# D_Output.net
KiCad netlist of a schematic drawn in Altium Designer
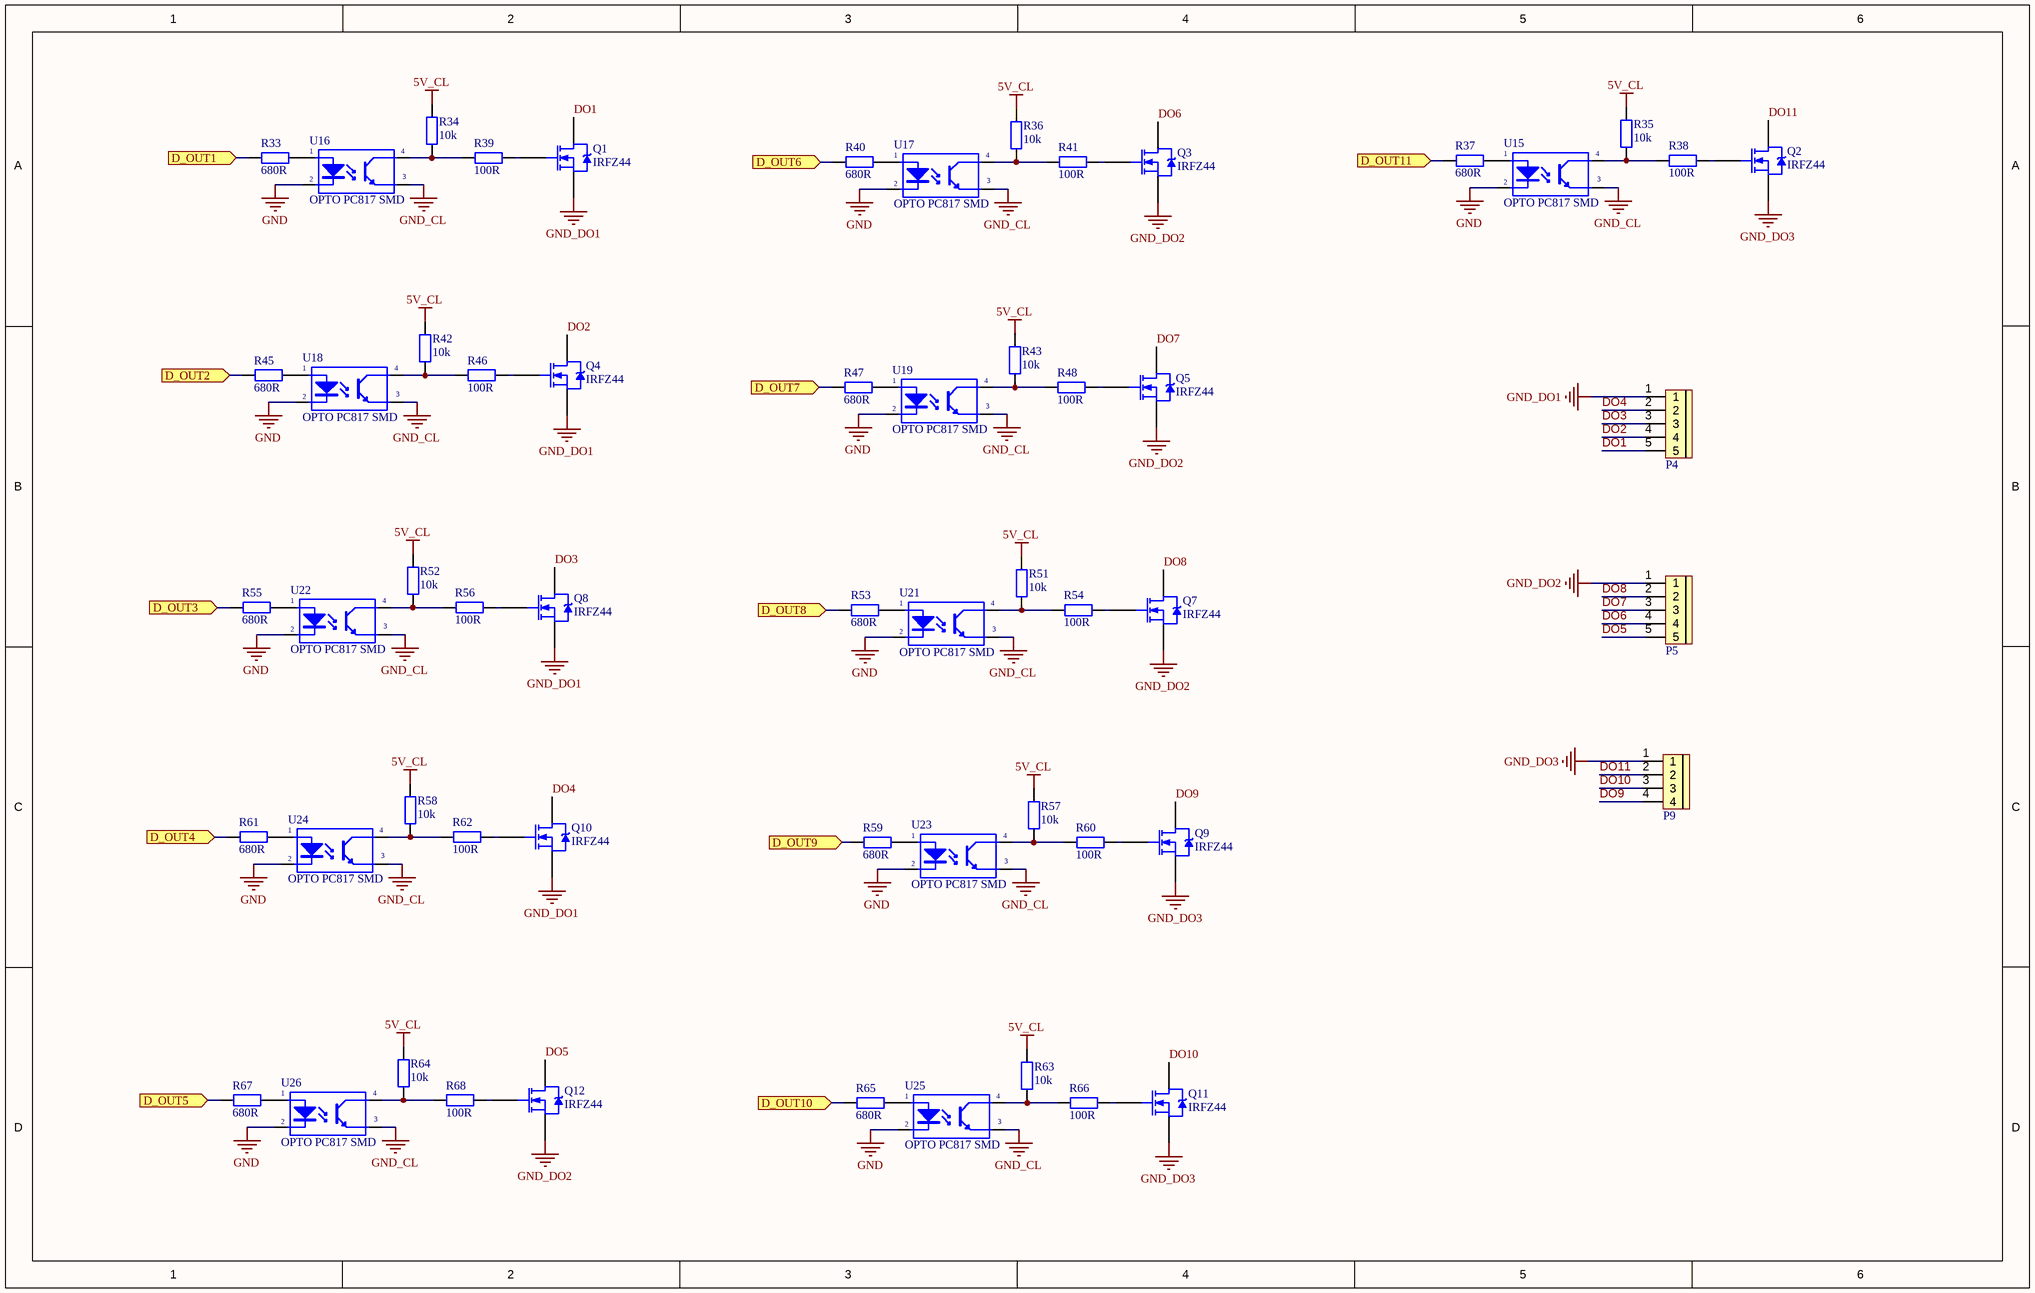
[diagram p0: D_Output.SchDoc]

(export (version "E")
  (design (tool "Eeschema 10.0.6"))
  (components
    (comp (ref "P4")
      (value "CON 5 EDG5.08")
      (footprint "CON 5 5EDG5.08")
      (description "Cắm")
      (libsource (lib "Altium_Lib_by_KhueNguyenCreator") (part "CON 5 EDG5.08"))
    )
    (comp (ref "P5")
      (value "CON 5 EDG5.08")
      (footprint "CON 5 5EDG5.08")
      (description "Cắm")
      (libsource (lib "Altium_Lib_by_KhueNguyenCreator") (part "CON 5 EDG5.08"))
    )
    (comp (ref "P9")
      (value "CON 4 EDG5.08")
      (footprint "CON 4 4EDG5.08")
      (description "Cắm")
      (libsource (lib "Altium_Lib_by_KhueNguyenCreator") (part "CON 4 EDG5.08"))
    )
    (comp (ref "Q1")
      (value "IRFZ44")
      (footprint "TO220")
      (description "N-Channel Power MOSFET")
      (libsource (lib "Altium_Lib_by_KhueNguyenCreator") (part "IRFZ44 DIP"))
    )
    (comp (ref "Q2")
      (value "IRFZ44")
      (footprint "TO220")
      (description "N-Channel Power MOSFET")
      (libsource (lib "Altium_Lib_by_KhueNguyenCreator") (part "IRFZ44 DIP"))
    )
    (comp (ref "Q3")
      (value "IRFZ44")
      (footprint "TO220")
      (description "N-Channel Power MOSFET")
      (libsource (lib "Altium_Lib_by_KhueNguyenCreator") (part "IRFZ44 DIP"))
    )
    (comp (ref "Q4")
      (value "IRFZ44")
      (footprint "TO220")
      (description "N-Channel Power MOSFET")
      (libsource (lib "Altium_Lib_by_KhueNguyenCreator") (part "IRFZ44 DIP"))
    )
    (comp (ref "Q5")
      (value "IRFZ44")
      (footprint "TO220")
      (description "N-Channel Power MOSFET")
      (libsource (lib "Altium_Lib_by_KhueNguyenCreator") (part "IRFZ44 DIP"))
    )
    (comp (ref "Q7")
      (value "IRFZ44")
      (footprint "TO220")
      (description "N-Channel Power MOSFET")
      (libsource (lib "Altium_Lib_by_KhueNguyenCreator") (part "IRFZ44 DIP"))
    )
    (comp (ref "Q8")
      (value "IRFZ44")
      (footprint "TO220")
      (description "N-Channel Power MOSFET")
      (libsource (lib "Altium_Lib_by_KhueNguyenCreator") (part "IRFZ44 DIP"))
    )
    (comp (ref "Q9")
      (value "IRFZ44")
      (footprint "TO220")
      (description "N-Channel Power MOSFET")
      (libsource (lib "Altium_Lib_by_KhueNguyenCreator") (part "IRFZ44 DIP"))
    )
    (comp (ref "Q10")
      (value "IRFZ44")
      (footprint "TO220")
      (description "N-Channel Power MOSFET")
      (libsource (lib "Altium_Lib_by_KhueNguyenCreator") (part "IRFZ44 DIP"))
    )
    (comp (ref "Q11")
      (value "IRFZ44")
      (footprint "TO220")
      (description "N-Channel Power MOSFET")
      (libsource (lib "Altium_Lib_by_KhueNguyenCreator") (part "IRFZ44 DIP"))
    )
    (comp (ref "Q12")
      (value "IRFZ44")
      (footprint "TO220")
      (description "N-Channel Power MOSFET")
      (libsource (lib "Altium_Lib_by_KhueNguyenCreator") (part "IRFZ44 DIP"))
    )
    (comp (ref "R33")
      (value "680R")
      (footprint "tro smd 0805")
      (description "Dán")
      (libsource (lib "Altium_Lib_by_KhueNguyenCreator") (part "Tro 0805 1% 680R"))
    )
    (comp (ref "R34")
      (value "10k")
      (footprint "tro smd 0805")
      (description "Dán")
      (libsource (lib "Altium_Lib_by_KhueNguyenCreator") (part "Tro 0805 1% 10k"))
    )
    (comp (ref "R35")
      (value "10k")
      (footprint "tro smd 0805")
      (description "Dán")
      (libsource (lib "Altium_Lib_by_KhueNguyenCreator") (part "Tro 0805 1% 10k"))
    )
    (comp (ref "R36")
      (value "10k")
      (footprint "tro smd 0805")
      (description "Dán")
      (libsource (lib "Altium_Lib_by_KhueNguyenCreator") (part "Tro 0805 1% 10k"))
    )
    (comp (ref "R37")
      (value "680R")
      (footprint "tro smd 0805")
      (description "Dán")
      (libsource (lib "Altium_Lib_by_KhueNguyenCreator") (part "Tro 0805 1% 680R"))
    )
    (comp (ref "R38")
      (value "100R")
      (footprint "tro smd 0805")
      (description "Dán")
      (libsource (lib "Altium_Lib_by_KhueNguyenCreator") (part "Tro 0805 5% 100R"))
    )
    (comp (ref "R39")
      (value "100R")
      (footprint "tro smd 0805")
      (description "Dán")
      (libsource (lib "Altium_Lib_by_KhueNguyenCreator") (part "Tro 0805 5% 100R"))
    )
    (comp (ref "R40")
      (value "680R")
      (footprint "tro smd 0805")
      (description "Dán")
      (libsource (lib "Altium_Lib_by_KhueNguyenCreator") (part "Tro 0805 1% 680R"))
    )
    (comp (ref "R41")
      (value "100R")
      (footprint "tro smd 0805")
      (description "Dán")
      (libsource (lib "Altium_Lib_by_KhueNguyenCreator") (part "Tro 0805 5% 100R"))
    )
    (comp (ref "R42")
      (value "10k")
      (footprint "tro smd 0805")
      (description "Dán")
      (libsource (lib "Altium_Lib_by_KhueNguyenCreator") (part "Tro 0805 1% 10k"))
    )
    (comp (ref "R43")
      (value "10k")
      (footprint "tro smd 0805")
      (description "Dán")
      (libsource (lib "Altium_Lib_by_KhueNguyenCreator") (part "Tro 0805 1% 10k"))
    )
    (comp (ref "R45")
      (value "680R")
      (footprint "tro smd 0805")
      (description "Dán")
      (libsource (lib "Altium_Lib_by_KhueNguyenCreator") (part "Tro 0805 1% 680R"))
    )
    (comp (ref "R46")
      (value "100R")
      (footprint "tro smd 0805")
      (description "Dán")
      (libsource (lib "Altium_Lib_by_KhueNguyenCreator") (part "Tro 0805 5% 100R"))
    )
    (comp (ref "R47")
      (value "680R")
      (footprint "tro smd 0805")
      (description "Dán")
      (libsource (lib "Altium_Lib_by_KhueNguyenCreator") (part "Tro 0805 1% 680R"))
    )
    (comp (ref "R48")
      (value "100R")
      (footprint "tro smd 0805")
      (description "Dán")
      (libsource (lib "Altium_Lib_by_KhueNguyenCreator") (part "Tro 0805 5% 100R"))
    )
    (comp (ref "R51")
      (value "10k")
      (footprint "tro smd 0805")
      (description "Dán")
      (libsource (lib "Altium_Lib_by_KhueNguyenCreator") (part "Tro 0805 1% 10k"))
    )
    (comp (ref "R52")
      (value "10k")
      (footprint "tro smd 0805")
      (description "Dán")
      (libsource (lib "Altium_Lib_by_KhueNguyenCreator") (part "Tro 0805 1% 10k"))
    )
    (comp (ref "R53")
      (value "680R")
      (footprint "tro smd 0805")
      (description "Dán")
      (libsource (lib "Altium_Lib_by_KhueNguyenCreator") (part "Tro 0805 1% 680R"))
    )
    (comp (ref "R54")
      (value "100R")
      (footprint "tro smd 0805")
      (description "Dán")
      (libsource (lib "Altium_Lib_by_KhueNguyenCreator") (part "Tro 0805 5% 100R"))
    )
    (comp (ref "R55")
      (value "680R")
      (footprint "tro smd 0805")
      (description "Dán")
      (libsource (lib "Altium_Lib_by_KhueNguyenCreator") (part "Tro 0805 1% 680R"))
    )
    (comp (ref "R56")
      (value "100R")
      (footprint "tro smd 0805")
      (description "Dán")
      (libsource (lib "Altium_Lib_by_KhueNguyenCreator") (part "Tro 0805 5% 100R"))
    )
    (comp (ref "R57")
      (value "10k")
      (footprint "tro smd 0805")
      (description "Dán")
      (libsource (lib "Altium_Lib_by_KhueNguyenCreator") (part "Tro 0805 1% 10k"))
    )
    (comp (ref "R58")
      (value "10k")
      (footprint "tro smd 0805")
      (description "Dán")
      (libsource (lib "Altium_Lib_by_KhueNguyenCreator") (part "Tro 0805 1% 10k"))
    )
    (comp (ref "R59")
      (value "680R")
      (footprint "tro smd 0805")
      (description "Dán")
      (libsource (lib "Altium_Lib_by_KhueNguyenCreator") (part "Tro 0805 1% 680R"))
    )
    (comp (ref "R60")
      (value "100R")
      (footprint "tro smd 0805")
      (description "Dán")
      (libsource (lib "Altium_Lib_by_KhueNguyenCreator") (part "Tro 0805 5% 100R"))
    )
    (comp (ref "R61")
      (value "680R")
      (footprint "tro smd 0805")
      (description "Dán")
      (libsource (lib "Altium_Lib_by_KhueNguyenCreator") (part "Tro 0805 1% 680R"))
    )
    (comp (ref "R62")
      (value "100R")
      (footprint "tro smd 0805")
      (description "Dán")
      (libsource (lib "Altium_Lib_by_KhueNguyenCreator") (part "Tro 0805 5% 100R"))
    )
    (comp (ref "R63")
      (value "10k")
      (footprint "tro smd 0805")
      (description "Dán")
      (libsource (lib "Altium_Lib_by_KhueNguyenCreator") (part "Tro 0805 1% 10k"))
    )
    (comp (ref "R64")
      (value "10k")
      (footprint "tro smd 0805")
      (description "Dán")
      (libsource (lib "Altium_Lib_by_KhueNguyenCreator") (part "Tro 0805 1% 10k"))
    )
    (comp (ref "R65")
      (value "680R")
      (footprint "tro smd 0805")
      (description "Dán")
      (libsource (lib "Altium_Lib_by_KhueNguyenCreator") (part "Tro 0805 1% 680R"))
    )
    (comp (ref "R66")
      (value "100R")
      (footprint "tro smd 0805")
      (description "Dán")
      (libsource (lib "Altium_Lib_by_KhueNguyenCreator") (part "Tro 0805 5% 100R"))
    )
    (comp (ref "R67")
      (value "680R")
      (footprint "tro smd 0805")
      (description "Dán")
      (libsource (lib "Altium_Lib_by_KhueNguyenCreator") (part "Tro 0805 1% 680R"))
    )
    (comp (ref "R68")
      (value "100R")
      (footprint "tro smd 0805")
      (description "Dán")
      (libsource (lib "Altium_Lib_by_KhueNguyenCreator") (part "Tro 0805 5% 100R"))
    )
    (comp (ref "U15")
      (value "OPTO PC817 SMD")
      (footprint "SOP4")
      (description "Single Opto")
      (libsource (lib "Altium_Lib_by_KhueNguyenCreator") (part "OPTO PC817 SMD"))
    )
    (comp (ref "U16")
      (value "OPTO PC817 SMD")
      (footprint "SOP4")
      (description "Single Opto")
      (libsource (lib "Altium_Lib_by_KhueNguyenCreator") (part "OPTO PC817 SMD"))
    )
    (comp (ref "U17")
      (value "OPTO PC817 SMD")
      (footprint "SOP4")
      (description "Single Opto")
      (libsource (lib "Altium_Lib_by_KhueNguyenCreator") (part "OPTO PC817 SMD"))
    )
    (comp (ref "U18")
      (value "OPTO PC817 SMD")
      (footprint "SOP4")
      (description "Single Opto")
      (libsource (lib "Altium_Lib_by_KhueNguyenCreator") (part "OPTO PC817 SMD"))
    )
    (comp (ref "U19")
      (value "OPTO PC817 SMD")
      (footprint "SOP4")
      (description "Single Opto")
      (libsource (lib "Altium_Lib_by_KhueNguyenCreator") (part "OPTO PC817 SMD"))
    )
    (comp (ref "U21")
      (value "OPTO PC817 SMD")
      (footprint "SOP4")
      (description "Single Opto")
      (libsource (lib "Altium_Lib_by_KhueNguyenCreator") (part "OPTO PC817 SMD"))
    )
    (comp (ref "U22")
      (value "OPTO PC817 SMD")
      (footprint "SOP4")
      (description "Single Opto")
      (libsource (lib "Altium_Lib_by_KhueNguyenCreator") (part "OPTO PC817 SMD"))
    )
    (comp (ref "U23")
      (value "OPTO PC817 SMD")
      (footprint "SOP4")
      (description "Single Opto")
      (libsource (lib "Altium_Lib_by_KhueNguyenCreator") (part "OPTO PC817 SMD"))
    )
    (comp (ref "U24")
      (value "OPTO PC817 SMD")
      (footprint "SOP4")
      (description "Single Opto")
      (libsource (lib "Altium_Lib_by_KhueNguyenCreator") (part "OPTO PC817 SMD"))
    )
    (comp (ref "U25")
      (value "OPTO PC817 SMD")
      (footprint "SOP4")
      (description "Single Opto")
      (libsource (lib "Altium_Lib_by_KhueNguyenCreator") (part "OPTO PC817 SMD"))
    )
    (comp (ref "U26")
      (value "OPTO PC817 SMD")
      (footprint "SOP4")
      (description "Single Opto")
      (libsource (lib "Altium_Lib_by_KhueNguyenCreator") (part "OPTO PC817 SMD"))
    )
  )
  (nets
    (net (code "1") (name "/DO1") (class "Default")
      (node (ref "P4") (pin "5") (pinfunction "5_5") (pintype "passive"))
      (node (ref "Q1") (pin "2") (pinfunction "D_2") (pintype "passive"))
    )
    (net (code "2") (name "/DO2") (class "Default")
      (node (ref "P4") (pin "4") (pinfunction "4_4") (pintype "passive"))
      (node (ref "Q4") (pin "2") (pinfunction "D_2") (pintype "passive"))
    )
    (net (code "3") (name "/DO3") (class "Default")
      (node (ref "P4") (pin "3") (pinfunction "3_3") (pintype "passive"))
      (node (ref "Q8") (pin "2") (pinfunction "D_2") (pintype "passive"))
    )
    (net (code "4") (name "/DO4") (class "Default")
      (node (ref "P4") (pin "2") (pinfunction "2_2") (pintype "passive"))
      (node (ref "Q10") (pin "2") (pinfunction "D_2") (pintype "passive"))
    )
    (net (code "5") (name "/DO5") (class "Default")
      (node (ref "P5") (pin "5") (pinfunction "5_5") (pintype "passive"))
      (node (ref "Q12") (pin "2") (pinfunction "D_2") (pintype "passive"))
    )
    (net (code "6") (name "/DO6") (class "Default")
      (node (ref "P5") (pin "4") (pinfunction "4_4") (pintype "passive"))
      (node (ref "Q3") (pin "2") (pinfunction "D_2") (pintype "passive"))
    )
    (net (code "7") (name "/DO7") (class "Default")
      (node (ref "P5") (pin "3") (pinfunction "3_3") (pintype "passive"))
      (node (ref "Q5") (pin "2") (pinfunction "D_2") (pintype "passive"))
    )
    (net (code "8") (name "/DO8") (class "Default")
      (node (ref "P5") (pin "2") (pinfunction "2_2") (pintype "passive"))
      (node (ref "Q7") (pin "2") (pinfunction "D_2") (pintype "passive"))
    )
    (net (code "9") (name "/DO9") (class "Default")
      (node (ref "P9") (pin "4") (pinfunction "4_4") (pintype "passive"))
      (node (ref "Q9") (pin "2") (pinfunction "D_2") (pintype "passive"))
    )
    (net (code "10") (name "/DO10") (class "Default")
      (node (ref "P9") (pin "3") (pinfunction "3_3") (pintype "passive"))
      (node (ref "Q11") (pin "2") (pinfunction "D_2") (pintype "passive"))
    )
    (net (code "11") (name "/DO11") (class "Default")
      (node (ref "P9") (pin "2") (pinfunction "2_2") (pintype "passive"))
      (node (ref "Q2") (pin "2") (pinfunction "D_2") (pintype "passive"))
    )
    (net (code "12") (name "/D_OUT1") (class "Default")
      (node (ref "R33") (pin "1") (pinfunction "1_1") (pintype "passive"))
    )
    (net (code "13") (name "/D_OUT2") (class "Default")
      (node (ref "R45") (pin "1") (pinfunction "1_1") (pintype "passive"))
    )
    (net (code "14") (name "/D_OUT3") (class "Default")
      (node (ref "R55") (pin "1") (pinfunction "1_1") (pintype "passive"))
    )
    (net (code "15") (name "/D_OUT4") (class "Default")
      (node (ref "R61") (pin "1") (pinfunction "1_1") (pintype "passive"))
    )
    (net (code "16") (name "/D_OUT5") (class "Default")
      (node (ref "R67") (pin "1") (pinfunction "1_1") (pintype "passive"))
    )
    (net (code "17") (name "/D_OUT6") (class "Default")
      (node (ref "R40") (pin "1") (pinfunction "1_1") (pintype "passive"))
    )
    (net (code "18") (name "/D_OUT7") (class "Default")
      (node (ref "R47") (pin "1") (pinfunction "1_1") (pintype "passive"))
    )
    (net (code "19") (name "/D_OUT8") (class "Default")
      (node (ref "R53") (pin "1") (pinfunction "1_1") (pintype "passive"))
    )
    (net (code "20") (name "/D_OUT9") (class "Default")
      (node (ref "R59") (pin "1") (pinfunction "1_1") (pintype "passive"))
    )
    (net (code "21") (name "/D_OUT10") (class "Default")
      (node (ref "R65") (pin "1") (pinfunction "1_1") (pintype "passive"))
    )
    (net (code "22") (name "/D_OUT11") (class "Default")
      (node (ref "R37") (pin "1") (pinfunction "1_1") (pintype "passive"))
    )
    (net (code "23") (name "5V_CL") (class "Default")
      (node (ref "R34") (pin "1") (pinfunction "1_1") (pintype "passive"))
      (node (ref "R35") (pin "1") (pinfunction "1_1") (pintype "passive"))
      (node (ref "R36") (pin "1") (pinfunction "1_1") (pintype "passive"))
      (node (ref "R42") (pin "1") (pinfunction "1_1") (pintype "passive"))
      (node (ref "R43") (pin "1") (pinfunction "1_1") (pintype "passive"))
      (node (ref "R51") (pin "1") (pinfunction "1_1") (pintype "passive"))
      (node (ref "R52") (pin "1") (pinfunction "1_1") (pintype "passive"))
      (node (ref "R57") (pin "1") (pinfunction "1_1") (pintype "passive"))
      (node (ref "R58") (pin "1") (pinfunction "1_1") (pintype "passive"))
      (node (ref "R63") (pin "1") (pinfunction "1_1") (pintype "passive"))
      (node (ref "R64") (pin "1") (pinfunction "1_1") (pintype "passive"))
    )
    (net (code "24") (name "GND") (class "Default")
      (node (ref "U15") (pin "2") (pinfunction "K_2") (pintype "passive"))
      (node (ref "U16") (pin "2") (pinfunction "K_2") (pintype "passive"))
      (node (ref "U17") (pin "2") (pinfunction "K_2") (pintype "passive"))
      (node (ref "U18") (pin "2") (pinfunction "K_2") (pintype "passive"))
      (node (ref "U19") (pin "2") (pinfunction "K_2") (pintype "passive"))
      (node (ref "U21") (pin "2") (pinfunction "K_2") (pintype "passive"))
      (node (ref "U22") (pin "2") (pinfunction "K_2") (pintype "passive"))
      (node (ref "U23") (pin "2") (pinfunction "K_2") (pintype "passive"))
      (node (ref "U24") (pin "2") (pinfunction "K_2") (pintype "passive"))
      (node (ref "U25") (pin "2") (pinfunction "K_2") (pintype "passive"))
      (node (ref "U26") (pin "2") (pinfunction "K_2") (pintype "passive"))
    )
    (net (code "25") (name "GND_CL") (class "Default")
      (node (ref "U15") (pin "3") (pinfunction "E_3") (pintype "passive"))
      (node (ref "U16") (pin "3") (pinfunction "E_3") (pintype "passive"))
      (node (ref "U17") (pin "3") (pinfunction "E_3") (pintype "passive"))
      (node (ref "U18") (pin "3") (pinfunction "E_3") (pintype "passive"))
      (node (ref "U19") (pin "3") (pinfunction "E_3") (pintype "passive"))
      (node (ref "U21") (pin "3") (pinfunction "E_3") (pintype "passive"))
      (node (ref "U22") (pin "3") (pinfunction "E_3") (pintype "passive"))
      (node (ref "U23") (pin "3") (pinfunction "E_3") (pintype "passive"))
      (node (ref "U24") (pin "3") (pinfunction "E_3") (pintype "passive"))
      (node (ref "U25") (pin "3") (pinfunction "E_3") (pintype "passive"))
      (node (ref "U26") (pin "3") (pinfunction "E_3") (pintype "passive"))
    )
    (net (code "26") (name "GND_DO1") (class "Default")
      (node (ref "P4") (pin "1") (pinfunction "1_1") (pintype "passive"))
      (node (ref "Q1") (pin "3") (pinfunction "S_3") (pintype "passive"))
      (node (ref "Q10") (pin "3") (pinfunction "S_3") (pintype "passive"))
      (node (ref "Q4") (pin "3") (pinfunction "S_3") (pintype "passive"))
      (node (ref "Q8") (pin "3") (pinfunction "S_3") (pintype "passive"))
    )
    (net (code "27") (name "GND_DO2") (class "Default")
      (node (ref "P5") (pin "1") (pinfunction "1_1") (pintype "passive"))
      (node (ref "Q12") (pin "3") (pinfunction "S_3") (pintype "passive"))
      (node (ref "Q3") (pin "3") (pinfunction "S_3") (pintype "passive"))
      (node (ref "Q5") (pin "3") (pinfunction "S_3") (pintype "passive"))
      (node (ref "Q7") (pin "3") (pinfunction "S_3") (pintype "passive"))
    )
    (net (code "28") (name "GND_DO3") (class "Default")
      (node (ref "P9") (pin "1") (pinfunction "1_1") (pintype "passive"))
      (node (ref "Q11") (pin "3") (pinfunction "S_3") (pintype "passive"))
      (node (ref "Q2") (pin "3") (pinfunction "S_3") (pintype "passive"))
      (node (ref "Q9") (pin "3") (pinfunction "S_3") (pintype "passive"))
    )
    (net (code "29") (name "Net-(Q1-G)") (class "Default")
      (node (ref "Q1") (pin "1") (pinfunction "G_1") (pintype "passive"))
      (node (ref "R39") (pin "2") (pinfunction "2_2") (pintype "passive"))
    )
    (net (code "30") (name "Net-(Q2-G)") (class "Default")
      (node (ref "Q2") (pin "1") (pinfunction "G_1") (pintype "passive"))
      (node (ref "R38") (pin "2") (pinfunction "2_2") (pintype "passive"))
    )
    (net (code "31") (name "Net-(Q3-G)") (class "Default")
      (node (ref "Q3") (pin "1") (pinfunction "G_1") (pintype "passive"))
      (node (ref "R41") (pin "2") (pinfunction "2_2") (pintype "passive"))
    )
    (net (code "32") (name "Net-(Q4-G)") (class "Default")
      (node (ref "Q4") (pin "1") (pinfunction "G_1") (pintype "passive"))
      (node (ref "R46") (pin "2") (pinfunction "2_2") (pintype "passive"))
    )
    (net (code "33") (name "Net-(Q5-G)") (class "Default")
      (node (ref "Q5") (pin "1") (pinfunction "G_1") (pintype "passive"))
      (node (ref "R48") (pin "2") (pinfunction "2_2") (pintype "passive"))
    )
    (net (code "34") (name "Net-(Q7-G)") (class "Default")
      (node (ref "Q7") (pin "1") (pinfunction "G_1") (pintype "passive"))
      (node (ref "R54") (pin "2") (pinfunction "2_2") (pintype "passive"))
    )
    (net (code "35") (name "Net-(Q8-G)") (class "Default")
      (node (ref "Q8") (pin "1") (pinfunction "G_1") (pintype "passive"))
      (node (ref "R56") (pin "2") (pinfunction "2_2") (pintype "passive"))
    )
    (net (code "36") (name "Net-(Q9-G)") (class "Default")
      (node (ref "Q9") (pin "1") (pinfunction "G_1") (pintype "passive"))
      (node (ref "R60") (pin "2") (pinfunction "2_2") (pintype "passive"))
    )
    (net (code "37") (name "Net-(Q10-G)") (class "Default")
      (node (ref "Q10") (pin "1") (pinfunction "G_1") (pintype "passive"))
      (node (ref "R62") (pin "2") (pinfunction "2_2") (pintype "passive"))
    )
    (net (code "38") (name "Net-(Q11-G)") (class "Default")
      (node (ref "Q11") (pin "1") (pinfunction "G_1") (pintype "passive"))
      (node (ref "R66") (pin "2") (pinfunction "2_2") (pintype "passive"))
    )
    (net (code "39") (name "Net-(Q12-G)") (class "Default")
      (node (ref "Q12") (pin "1") (pinfunction "G_1") (pintype "passive"))
      (node (ref "R68") (pin "2") (pinfunction "2_2") (pintype "passive"))
    )
    (net (code "40") (name "Net-(U15-A)") (class "Default")
      (node (ref "R37") (pin "2") (pinfunction "2_2") (pintype "passive"))
      (node (ref "U15") (pin "1") (pinfunction "A_1") (pintype "passive"))
    )
    (net (code "41") (name "Net-(U15-C)") (class "Default")
      (node (ref "R35") (pin "2") (pinfunction "2_2") (pintype "passive"))
      (node (ref "R38") (pin "1") (pinfunction "1_1") (pintype "passive"))
      (node (ref "U15") (pin "4") (pinfunction "C_4") (pintype "passive"))
    )
    (net (code "42") (name "Net-(U16-A)") (class "Default")
      (node (ref "R33") (pin "2") (pinfunction "2_2") (pintype "passive"))
      (node (ref "U16") (pin "1") (pinfunction "A_1") (pintype "passive"))
    )
    (net (code "43") (name "Net-(U16-C)") (class "Default")
      (node (ref "R34") (pin "2") (pinfunction "2_2") (pintype "passive"))
      (node (ref "R39") (pin "1") (pinfunction "1_1") (pintype "passive"))
      (node (ref "U16") (pin "4") (pinfunction "C_4") (pintype "passive"))
    )
    (net (code "44") (name "Net-(U17-A)") (class "Default")
      (node (ref "R40") (pin "2") (pinfunction "2_2") (pintype "passive"))
      (node (ref "U17") (pin "1") (pinfunction "A_1") (pintype "passive"))
    )
    (net (code "45") (name "Net-(U17-C)") (class "Default")
      (node (ref "R36") (pin "2") (pinfunction "2_2") (pintype "passive"))
      (node (ref "R41") (pin "1") (pinfunction "1_1") (pintype "passive"))
      (node (ref "U17") (pin "4") (pinfunction "C_4") (pintype "passive"))
    )
    (net (code "46") (name "Net-(U18-A)") (class "Default")
      (node (ref "R45") (pin "2") (pinfunction "2_2") (pintype "passive"))
      (node (ref "U18") (pin "1") (pinfunction "A_1") (pintype "passive"))
    )
    (net (code "47") (name "Net-(U18-C)") (class "Default")
      (node (ref "R42") (pin "2") (pinfunction "2_2") (pintype "passive"))
      (node (ref "R46") (pin "1") (pinfunction "1_1") (pintype "passive"))
      (node (ref "U18") (pin "4") (pinfunction "C_4") (pintype "passive"))
    )
    (net (code "48") (name "Net-(U19-A)") (class "Default")
      (node (ref "R47") (pin "2") (pinfunction "2_2") (pintype "passive"))
      (node (ref "U19") (pin "1") (pinfunction "A_1") (pintype "passive"))
    )
    (net (code "49") (name "Net-(U19-C)") (class "Default")
      (node (ref "R43") (pin "2") (pinfunction "2_2") (pintype "passive"))
      (node (ref "R48") (pin "1") (pinfunction "1_1") (pintype "passive"))
      (node (ref "U19") (pin "4") (pinfunction "C_4") (pintype "passive"))
    )
    (net (code "50") (name "Net-(U21-A)") (class "Default")
      (node (ref "R53") (pin "2") (pinfunction "2_2") (pintype "passive"))
      (node (ref "U21") (pin "1") (pinfunction "A_1") (pintype "passive"))
    )
    (net (code "51") (name "Net-(U21-C)") (class "Default")
      (node (ref "R51") (pin "2") (pinfunction "2_2") (pintype "passive"))
      (node (ref "R54") (pin "1") (pinfunction "1_1") (pintype "passive"))
      (node (ref "U21") (pin "4") (pinfunction "C_4") (pintype "passive"))
    )
    (net (code "52") (name "Net-(U22-A)") (class "Default")
      (node (ref "R55") (pin "2") (pinfunction "2_2") (pintype "passive"))
      (node (ref "U22") (pin "1") (pinfunction "A_1") (pintype "passive"))
    )
    (net (code "53") (name "Net-(U22-C)") (class "Default")
      (node (ref "R52") (pin "2") (pinfunction "2_2") (pintype "passive"))
      (node (ref "R56") (pin "1") (pinfunction "1_1") (pintype "passive"))
      (node (ref "U22") (pin "4") (pinfunction "C_4") (pintype "passive"))
    )
    (net (code "54") (name "Net-(U23-A)") (class "Default")
      (node (ref "R59") (pin "2") (pinfunction "2_2") (pintype "passive"))
      (node (ref "U23") (pin "1") (pinfunction "A_1") (pintype "passive"))
    )
    (net (code "55") (name "Net-(U23-C)") (class "Default")
      (node (ref "R57") (pin "2") (pinfunction "2_2") (pintype "passive"))
      (node (ref "R60") (pin "1") (pinfunction "1_1") (pintype "passive"))
      (node (ref "U23") (pin "4") (pinfunction "C_4") (pintype "passive"))
    )
    (net (code "56") (name "Net-(U24-A)") (class "Default")
      (node (ref "R61") (pin "2") (pinfunction "2_2") (pintype "passive"))
      (node (ref "U24") (pin "1") (pinfunction "A_1") (pintype "passive"))
    )
    (net (code "57") (name "Net-(U24-C)") (class "Default")
      (node (ref "R58") (pin "2") (pinfunction "2_2") (pintype "passive"))
      (node (ref "R62") (pin "1") (pinfunction "1_1") (pintype "passive"))
      (node (ref "U24") (pin "4") (pinfunction "C_4") (pintype "passive"))
    )
    (net (code "58") (name "Net-(U25-A)") (class "Default")
      (node (ref "R65") (pin "2") (pinfunction "2_2") (pintype "passive"))
      (node (ref "U25") (pin "1") (pinfunction "A_1") (pintype "passive"))
    )
    (net (code "59") (name "Net-(U25-C)") (class "Default")
      (node (ref "R63") (pin "2") (pinfunction "2_2") (pintype "passive"))
      (node (ref "R66") (pin "1") (pinfunction "1_1") (pintype "passive"))
      (node (ref "U25") (pin "4") (pinfunction "C_4") (pintype "passive"))
    )
    (net (code "60") (name "Net-(U26-A)") (class "Default")
      (node (ref "R67") (pin "2") (pinfunction "2_2") (pintype "passive"))
      (node (ref "U26") (pin "1") (pinfunction "A_1") (pintype "passive"))
    )
    (net (code "61") (name "Net-(U26-C)") (class "Default")
      (node (ref "R64") (pin "2") (pinfunction "2_2") (pintype "passive"))
      (node (ref "R68") (pin "1") (pinfunction "1_1") (pintype "passive"))
      (node (ref "U26") (pin "4") (pinfunction "C_4") (pintype "passive"))
    )
  )
)
